# TK-KB1.net
KiCad netlist of a schematic drawn in EasyEDA Pro
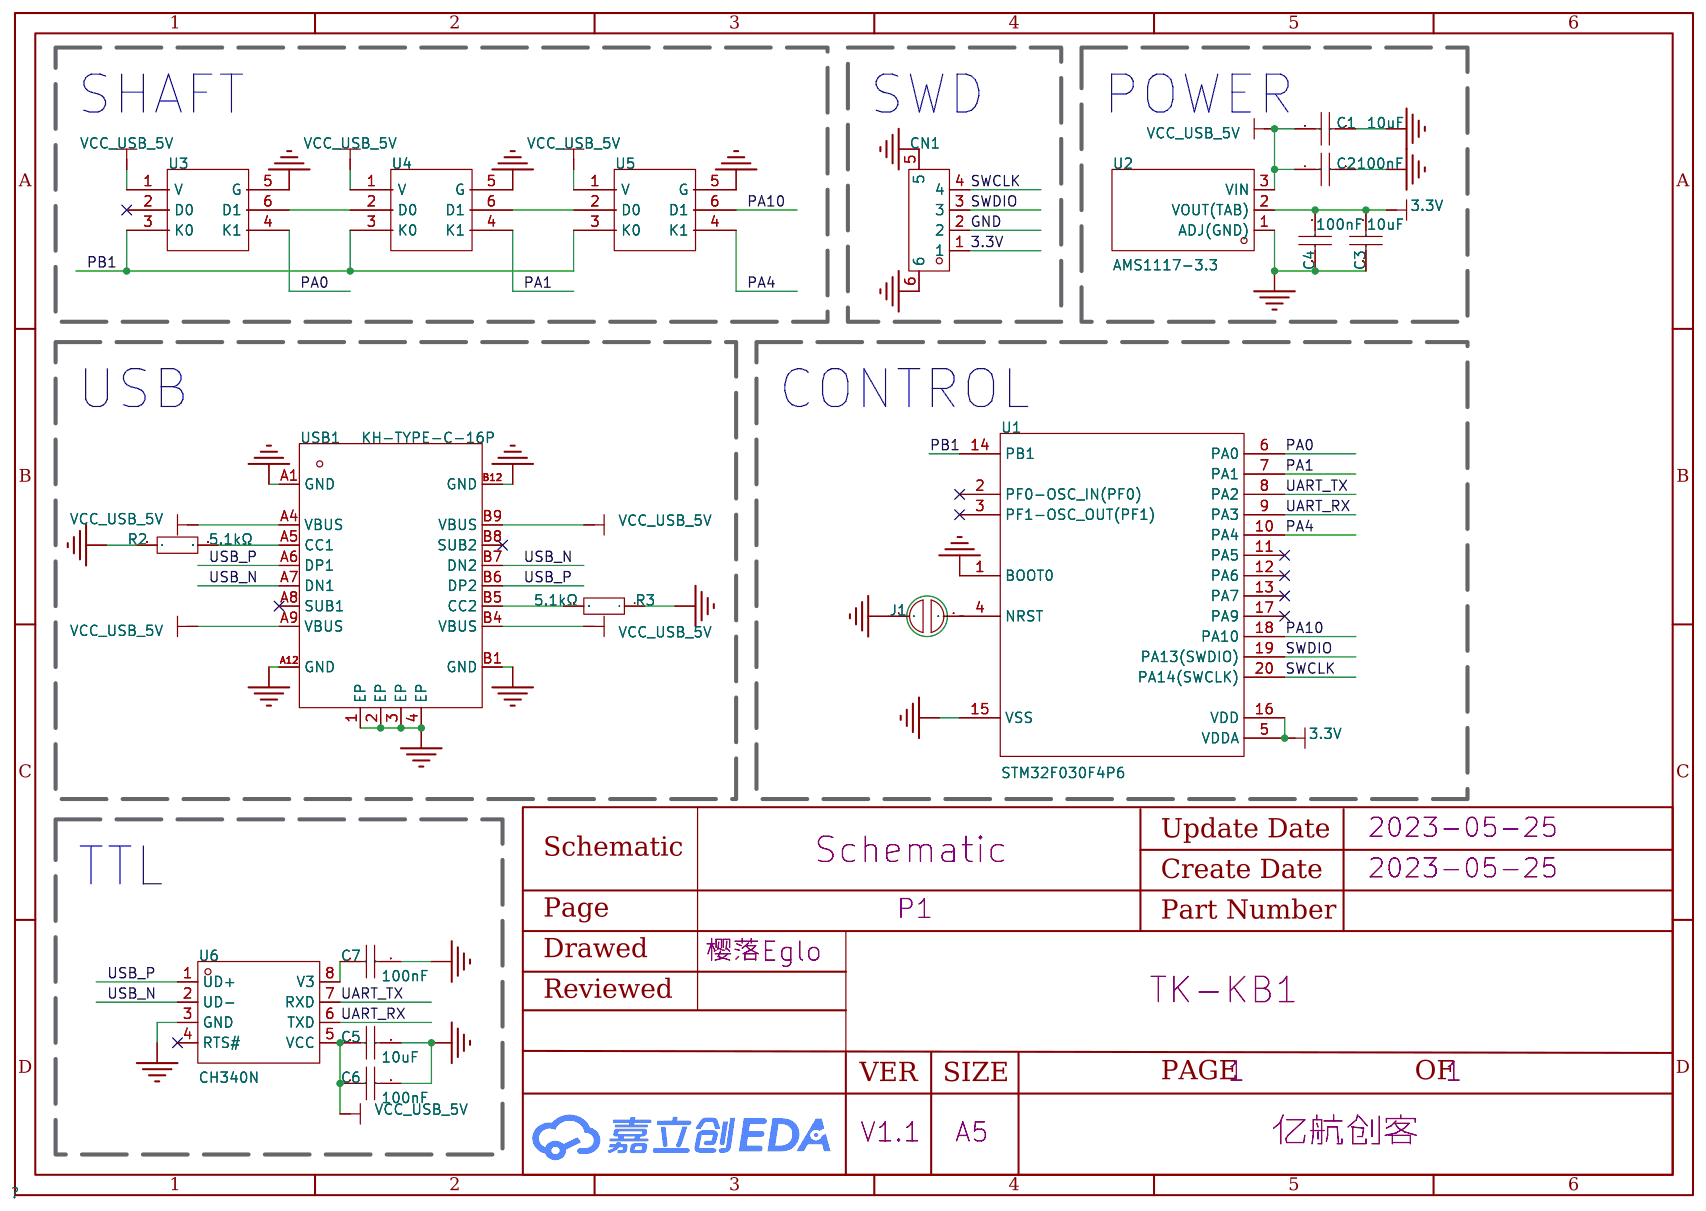
[diagram p0: schematic sheet]

(export (version "E")
  (design (tool "Eeschema 10.0.6"))
  (components
    (comp (ref "C1")
      (value "10uF")
      (footprint "easyedapro:C0402")
      (description "容值:10uF;精度:±20%;额定电压:6.3V;材质(温度系数):X5R;")
      (fields
        (field (name "Manufacturer Part") "CL05A106MQ5NUNC")
        (field (name "Manufacturer") "SAMSUNG(三星)")
      )
      (libsource (lib "easyedapro") (part "CL05A106MQ5NUNC"))
    )
    (comp (ref "C2")
      (value "100nF")
      (footprint "easyedapro:C0402")
      (description "容值:100nF;精度:±10%;额定电压:16V;材质(温度系数):X7R;")
      (fields
        (field (name "Manufacturer Part") "CL05B104KO5NNNC")
        (field (name "Manufacturer") "SAMSUNG(三星)")
      )
      (libsource (lib "easyedapro") (part "CL05B104KO5NNNC"))
    )
    (comp (ref "C3")
      (value "10uF")
      (footprint "easyedapro:C0402")
      (description "容值:10uF;精度:±20%;额定电压:6.3V;材质(温度系数):X5R;")
      (fields
        (field (name "Manufacturer Part") "CL05A106MQ5NUNC")
        (field (name "Manufacturer") "SAMSUNG(三星)")
      )
      (libsource (lib "easyedapro") (part "CL05A106MQ5NUNC"))
    )
    (comp (ref "C4")
      (value "100nF")
      (footprint "easyedapro:C0402")
      (description "容值:100nF;精度:±10%;额定电压:16V;材质(温度系数):X7R;")
      (fields
        (field (name "Manufacturer Part") "CL05B104KO5NNNC")
        (field (name "Manufacturer") "SAMSUNG(三星)")
      )
      (libsource (lib "easyedapro") (part "CL05B104KO5NNNC"))
    )
    (comp (ref "C5")
      (value "10uF")
      (footprint "easyedapro:C0402")
      (description "容值:10uF;精度:±20%;额定电压:6.3V;材质(温度系数):X5R;")
      (fields
        (field (name "Manufacturer Part") "CL05A106MQ5NUNC")
        (field (name "Manufacturer") "SAMSUNG(三星)")
      )
      (libsource (lib "easyedapro") (part "CL05A106MQ5NUNC"))
    )
    (comp (ref "C6")
      (value "100nF")
      (footprint "easyedapro:C0402")
      (description "容值:100nF;精度:±10%;额定电压:16V;材质(温度系数):X7R;")
      (fields
        (field (name "Manufacturer Part") "CL05B104KO5NNNC")
        (field (name "Manufacturer") "SAMSUNG(三星)")
      )
      (libsource (lib "easyedapro") (part "CL05B104KO5NNNC"))
    )
    (comp (ref "C7")
      (value "100nF")
      (footprint "easyedapro:C0402")
      (description "容值:100nF;精度:±10%;额定电压:16V;材质(温度系数):X7R;")
      (fields
        (field (name "Manufacturer Part") "CL05B104KO5NNNC")
        (field (name "Manufacturer") "SAMSUNG(三星)")
      )
      (libsource (lib "easyedapro") (part "CL05B104KO5NNNC"))
    )
    (comp (ref "CN1")
      (value "HDGC1002WR-S-4P")
      (footprint "easyedapro:CONN-SMD_4P-P1.00_HDGC_HDGC1002WR-S-4P")
      (description "SH1.0针座卧贴 4P")
      (fields (field (name "Manufacturer") "HDGC(华德共创)"))
      (libsource (lib "easyedapro") (part "HDGC1002WR-S-4P"))
    )
    (comp (ref "J1")
      (value "~")
      (footprint "easyedapro:R0402")
      (description "飞线")
      (libsource (lib "easyedapro") (part "Jumper"))
    )
    (comp (ref "R2")
      (value "5.1kΩ")
      (footprint "easyedapro:R0402")
      (description "电阻类型:厚膜电阻;阻值:5.1kΩ;精度:±1%;功率:62.5mW;")
      (fields
        (field (name "Manufacturer Part") "0402WGF5101TCE")
        (field (name "Manufacturer") "UNI-ROYAL(厚声)")
      )
      (libsource (lib "easyedapro") (part "0402WGF5101TCE"))
    )
    (comp (ref "R3")
      (value "5.1kΩ")
      (footprint "easyedapro:R0402")
      (description "电阻类型:厚膜电阻;阻值:5.1kΩ;精度:±1%;功率:62.5mW;")
      (fields
        (field (name "Manufacturer Part") "0402WGF5101TCE")
        (field (name "Manufacturer") "UNI-ROYAL(厚声)")
      )
      (libsource (lib "easyedapro") (part "0402WGF5101TCE"))
    )
    (comp (ref "U1")
      (value "STM32F030F4P6")
      (footprint "easyedapro:TSSOP-20_L6.5-W4.4-P0.65-LS6.4-BL")
      (description "CPU内核:ARM Cortex-M0;CPU最大主频:48MHz;程序存储容量:16KB;程序存储器类型:FLASH;RAM总容量:4KB;GPIO端口数量:15;")
      (fields (field (name "Manufacturer") "ST(意法半导体)"))
      (libsource (lib "easyedapro") (part "STM32F030F4P6"))
    )
    (comp (ref "U2")
      (value "AMS1117-3.3")
      (footprint "easyedapro:SOT-89_L4.5-W2.5-P1.50-LS4.2-BR")
      (description "输出类型:固定;输出极性:正;最大输入电压:18V;输出电压:3.3V;输出电流:1A;电源纹波抑制比(PSRR):60dB@(120Hz);")
      (fields (field (name "Manufacturer") "UMW(广东友台半导体)"))
      (libsource (lib "easyedapro") (part "AMS1117-3.3_C347256"))
    )
    (comp (ref "U3")
      (value "~")
      (footprint "easyedapro:凯华轴座+3528反贴灯")
      (description "缺口在右下")
      (libsource (lib "easyedapro") (part "凯华轴座+3528反贴灯"))
    )
    (comp (ref "U4")
      (value "~")
      (footprint "easyedapro:凯华轴座+3528反贴灯")
      (description "缺口在右下")
      (libsource (lib "easyedapro") (part "凯华轴座+3528反贴灯"))
    )
    (comp (ref "U5")
      (value "~")
      (footprint "easyedapro:凯华轴座+3528反贴灯")
      (description "缺口在右下")
      (libsource (lib "easyedapro") (part "凯华轴座+3528反贴灯"))
    )
    (comp (ref "U6")
      (value "CH340N")
      (footprint "easyedapro:SOP-8_L4.9-W3.9-P1.27-LS6.0-BL")
      (fields (field (name "Manufacturer") "WCH(南京沁恒)"))
      (libsource (lib "easyedapro") (part "CH340N_C2977777"))
    )
    (comp (ref "USB1")
      (value "KH-TYPE-C-16P")
      (footprint "easyedapro:USB-C-SMD_KH-TYPE-C-16P")
      (description "连接器类型:Type-C;标准:-;公母:母座;触点数量:16;端口数量:1;安装方式:卧贴;额定电流 - 电源:3A;工作温度范围:-40°C~+85°C;")
      (fields (field (name "Manufacturer") "kinghelm(金航标)"))
      (libsource (lib "easyedapro") (part "KH-TYPE-C-16P"))
    )
  )
  (nets
    (net (code "1") (name "/PA0") (class "Default")
      (node (ref "U1") (pin "6") (pinfunction "PA0_6") (pintype "bidirectional"))
      (node (ref "U3") (pin "4") (pinfunction "K1_4") (pintype "input"))
    )
    (net (code "2") (name "/PA1") (class "Default")
      (node (ref "U1") (pin "7") (pinfunction "PA1_7") (pintype "bidirectional"))
      (node (ref "U4") (pin "4") (pinfunction "K1_4") (pintype "input"))
    )
    (net (code "3") (name "/PA4") (class "Default")
      (node (ref "U1") (pin "10") (pinfunction "PA4_10") (pintype "bidirectional"))
      (node (ref "U5") (pin "4") (pinfunction "K1_4") (pintype "input"))
    )
    (net (code "4") (name "/PA10") (class "Default")
      (node (ref "U1") (pin "18") (pinfunction "PA10_18") (pintype "bidirectional"))
      (node (ref "U5") (pin "6") (pinfunction "D1_6") (pintype "input"))
    )
    (net (code "5") (name "/PB1") (class "Default")
      (node (ref "U1") (pin "14") (pinfunction "PB1_14") (pintype "bidirectional"))
      (node (ref "U3") (pin "3") (pinfunction "K0_3") (pintype "input"))
      (node (ref "U4") (pin "3") (pinfunction "K0_3") (pintype "input"))
      (node (ref "U5") (pin "3") (pinfunction "K0_3") (pintype "input"))
    )
    (net (code "6") (name "/SWCLK") (class "Default")
      (node (ref "CN1") (pin "4") (pinfunction "4_4") (pintype "input"))
      (node (ref "U1") (pin "20") (pinfunction "PA14(SWCLK)_20") (pintype "bidirectional"))
    )
    (net (code "7") (name "/SWDIO") (class "Default")
      (node (ref "CN1") (pin "3") (pinfunction "3_3") (pintype "input"))
      (node (ref "U1") (pin "19") (pinfunction "PA13(SWDIO)_19") (pintype "bidirectional"))
    )
    (net (code "8") (name "/UART_RX") (class "Default")
      (node (ref "U1") (pin "9") (pinfunction "PA3_9") (pintype "bidirectional"))
      (node (ref "U6") (pin "6") (pinfunction "TXD_6") (pintype "input"))
    )
    (net (code "9") (name "/UART_TX") (class "Default")
      (node (ref "U1") (pin "8") (pinfunction "PA2_8") (pintype "bidirectional"))
      (node (ref "U6") (pin "7") (pinfunction "RXD_7") (pintype "input"))
    )
    (net (code "10") (name "/USB_N") (class "Default")
      (node (ref "U6") (pin "2") (pinfunction "UD-_2") (pintype "input"))
      (node (ref "USB1") (pin "A7") (pinfunction "DN1_A7") (pintype "input"))
      (node (ref "USB1") (pin "B7") (pinfunction "DN2_B7") (pintype "input"))
    )
    (net (code "11") (name "/USB_P") (class "Default")
      (node (ref "U6") (pin "1") (pinfunction "UD+_1") (pintype "input"))
      (node (ref "USB1") (pin "A6") (pinfunction "DP1_A6") (pintype "input"))
      (node (ref "USB1") (pin "B6") (pinfunction "DP2_B6") (pintype "input"))
    )
    (net (code "12") (name "3.3V") (class "Default")
      (node (ref "C3") (pin "1") (pinfunction "1_1") (pintype "input"))
      (node (ref "C4") (pin "1") (pinfunction "1_1") (pintype "input"))
      (node (ref "CN1") (pin "1") (pinfunction "1_1") (pintype "input"))
      (node (ref "U1") (pin "16") (pinfunction "VDD_16") (pintype "input"))
      (node (ref "U1") (pin "5") (pinfunction "VDDA_5") (pintype "input"))
      (node (ref "U2") (pin "2") (pinfunction "VOUT(TAB)_2") (pintype "input"))
    )
    (net (code "13") (name "GND") (class "Default")
      (node (ref "C1") (pin "2") (pinfunction "2_2") (pintype "input"))
      (node (ref "C2") (pin "2") (pinfunction "2_2") (pintype "input"))
      (node (ref "C3") (pin "2") (pinfunction "2_2") (pintype "input"))
      (node (ref "C4") (pin "2") (pinfunction "2_2") (pintype "input"))
      (node (ref "C5") (pin "2") (pinfunction "2_2") (pintype "input"))
      (node (ref "C6") (pin "2") (pinfunction "2_2") (pintype "input"))
      (node (ref "C7") (pin "2") (pinfunction "2_2") (pintype "input"))
      (node (ref "CN1") (pin "2") (pinfunction "2_2") (pintype "input"))
      (node (ref "CN1") (pin "5") (pinfunction "5_5") (pintype "input"))
      (node (ref "CN1") (pin "6") (pinfunction "6_6") (pintype "input"))
      (node (ref "J1") (pin "1") (pinfunction "1_1") (pintype "input"))
      (node (ref "R2") (pin "1") (pinfunction "1_1") (pintype "input"))
      (node (ref "R3") (pin "1") (pinfunction "1_1") (pintype "input"))
      (node (ref "U1") (pin "1") (pinfunction "BOOT0_1") (pintype "input"))
      (node (ref "U1") (pin "15") (pinfunction "VSS_15") (pintype "input"))
      (node (ref "U2") (pin "1") (pinfunction "ADJ(GND)_1") (pintype "input"))
      (node (ref "U3") (pin "5") (pinfunction "G_5") (pintype "input"))
      (node (ref "U4") (pin "5") (pinfunction "G_5") (pintype "input"))
      (node (ref "U5") (pin "5") (pinfunction "G_5") (pintype "input"))
      (node (ref "U6") (pin "3") (pinfunction "GND_3") (pintype "input"))
      (node (ref "USB1") (pin "1") (pinfunction "EP_1") (pintype "input"))
      (node (ref "USB1") (pin "2") (pinfunction "EP_2") (pintype "input"))
      (node (ref "USB1") (pin "3") (pinfunction "EP_3") (pintype "input"))
      (node (ref "USB1") (pin "4") (pinfunction "EP_4") (pintype "input"))
      (node (ref "USB1") (pin "A1") (pinfunction "GND_A1") (pintype "input"))
      (node (ref "USB1") (pin "A12") (pinfunction "GND_A12") (pintype "input"))
      (node (ref "USB1") (pin "B1") (pinfunction "GND_B1") (pintype "input"))
      (node (ref "USB1") (pin "B12") (pinfunction "GND_B12") (pintype "input"))
    )
    (net (code "14") (name "Net-(U1-NRST)") (class "Default")
      (node (ref "J1") (pin "2") (pinfunction "2_2") (pintype "input"))
      (node (ref "U1") (pin "4") (pinfunction "NRST_4") (pintype "bidirectional"))
    )
    (net (code "15") (name "Net-(U3-D1)") (class "Default")
      (node (ref "U3") (pin "6") (pinfunction "D1_6") (pintype "input"))
      (node (ref "U4") (pin "2") (pinfunction "D0_2") (pintype "input"))
    )
    (net (code "16") (name "Net-(U4-D1)") (class "Default")
      (node (ref "U4") (pin "6") (pinfunction "D1_6") (pintype "input"))
      (node (ref "U5") (pin "2") (pinfunction "D0_2") (pintype "input"))
    )
    (net (code "17") (name "Net-(U6-V3)") (class "Default")
      (node (ref "C7") (pin "1") (pinfunction "1_1") (pintype "input"))
      (node (ref "U6") (pin "8") (pinfunction "V3_8") (pintype "input"))
    )
    (net (code "18") (name "Net-(USB1-CC1)") (class "Default")
      (node (ref "R2") (pin "2") (pinfunction "2_2") (pintype "input"))
      (node (ref "USB1") (pin "A5") (pinfunction "CC1_A5") (pintype "input"))
    )
    (net (code "19") (name "Net-(USB1-CC2)") (class "Default")
      (node (ref "R3") (pin "2") (pinfunction "2_2") (pintype "input"))
      (node (ref "USB1") (pin "B5") (pinfunction "CC2_B5") (pintype "input"))
    )
    (net (code "20") (name "VCC_USB_5V") (class "Default")
      (node (ref "C1") (pin "1") (pinfunction "1_1") (pintype "input"))
      (node (ref "C2") (pin "1") (pinfunction "1_1") (pintype "input"))
      (node (ref "C5") (pin "1") (pinfunction "1_1") (pintype "input"))
      (node (ref "C6") (pin "1") (pinfunction "1_1") (pintype "input"))
      (node (ref "U2") (pin "3") (pinfunction "VIN_3") (pintype "input"))
      (node (ref "U3") (pin "1") (pinfunction "V_1") (pintype "input"))
      (node (ref "U4") (pin "1") (pinfunction "V_1") (pintype "input"))
      (node (ref "U5") (pin "1") (pinfunction "V_1") (pintype "input"))
      (node (ref "U6") (pin "5") (pinfunction "VCC_5") (pintype "input"))
      (node (ref "USB1") (pin "A4") (pinfunction "VBUS_A4") (pintype "input"))
      (node (ref "USB1") (pin "A9") (pinfunction "VBUS_A9") (pintype "input"))
      (node (ref "USB1") (pin "B4") (pinfunction "VBUS_B4") (pintype "input"))
      (node (ref "USB1") (pin "B9") (pinfunction "VBUS_B9") (pintype "input"))
    )
    (net (code "21") (name "unconnected-(U1-PA5-Pad11)") (class "Default")
      (node (ref "U1") (pin "11") (pinfunction "PA5_11") (pintype "bidirectional+no_connect"))
    )
    (net (code "22") (name "unconnected-(U1-PA6-Pad12)") (class "Default")
      (node (ref "U1") (pin "12") (pinfunction "PA6_12") (pintype "bidirectional+no_connect"))
    )
    (net (code "23") (name "unconnected-(U1-PA7-Pad13)") (class "Default")
      (node (ref "U1") (pin "13") (pinfunction "PA7_13") (pintype "bidirectional+no_connect"))
    )
    (net (code "24") (name "unconnected-(U1-PA9-Pad17)") (class "Default")
      (node (ref "U1") (pin "17") (pinfunction "PA9_17") (pintype "bidirectional+no_connect"))
    )
    (net (code "25") (name "unconnected-(U1-PF0-OSC_IN(PF0)-Pad2)") (class "Default")
      (node (ref "U1") (pin "2") (pinfunction "PF0-OSC_IN(PF0)_2") (pintype "bidirectional+no_connect"))
    )
    (net (code "26") (name "unconnected-(U1-PF1-OSC_OUT(PF1)-Pad3)") (class "Default")
      (node (ref "U1") (pin "3") (pinfunction "PF1-OSC_OUT(PF1)_3") (pintype "bidirectional+no_connect"))
    )
    (net (code "27") (name "unconnected-(U3-D0-Pad2)") (class "Default")
      (node (ref "U3") (pin "2") (pinfunction "D0_2") (pintype "input+no_connect"))
    )
    (net (code "28") (name "unconnected-(U6-RTS#-Pad4)") (class "Default")
      (node (ref "U6") (pin "4") (pinfunction "RTS#_4") (pintype "input+no_connect"))
    )
    (net (code "29") (name "unconnected-(USB1-SUB1-PadA8)") (class "Default")
      (node (ref "USB1") (pin "A8") (pinfunction "SUB1_A8") (pintype "input+no_connect"))
    )
    (net (code "30") (name "unconnected-(USB1-SUB2-PadB8)") (class "Default")
      (node (ref "USB1") (pin "B8") (pinfunction "SUB2_B8") (pintype "input+no_connect"))
    )
  )
)
